# ide-8bit.net
KiCad netlist of a schematic drawn in EAGLE
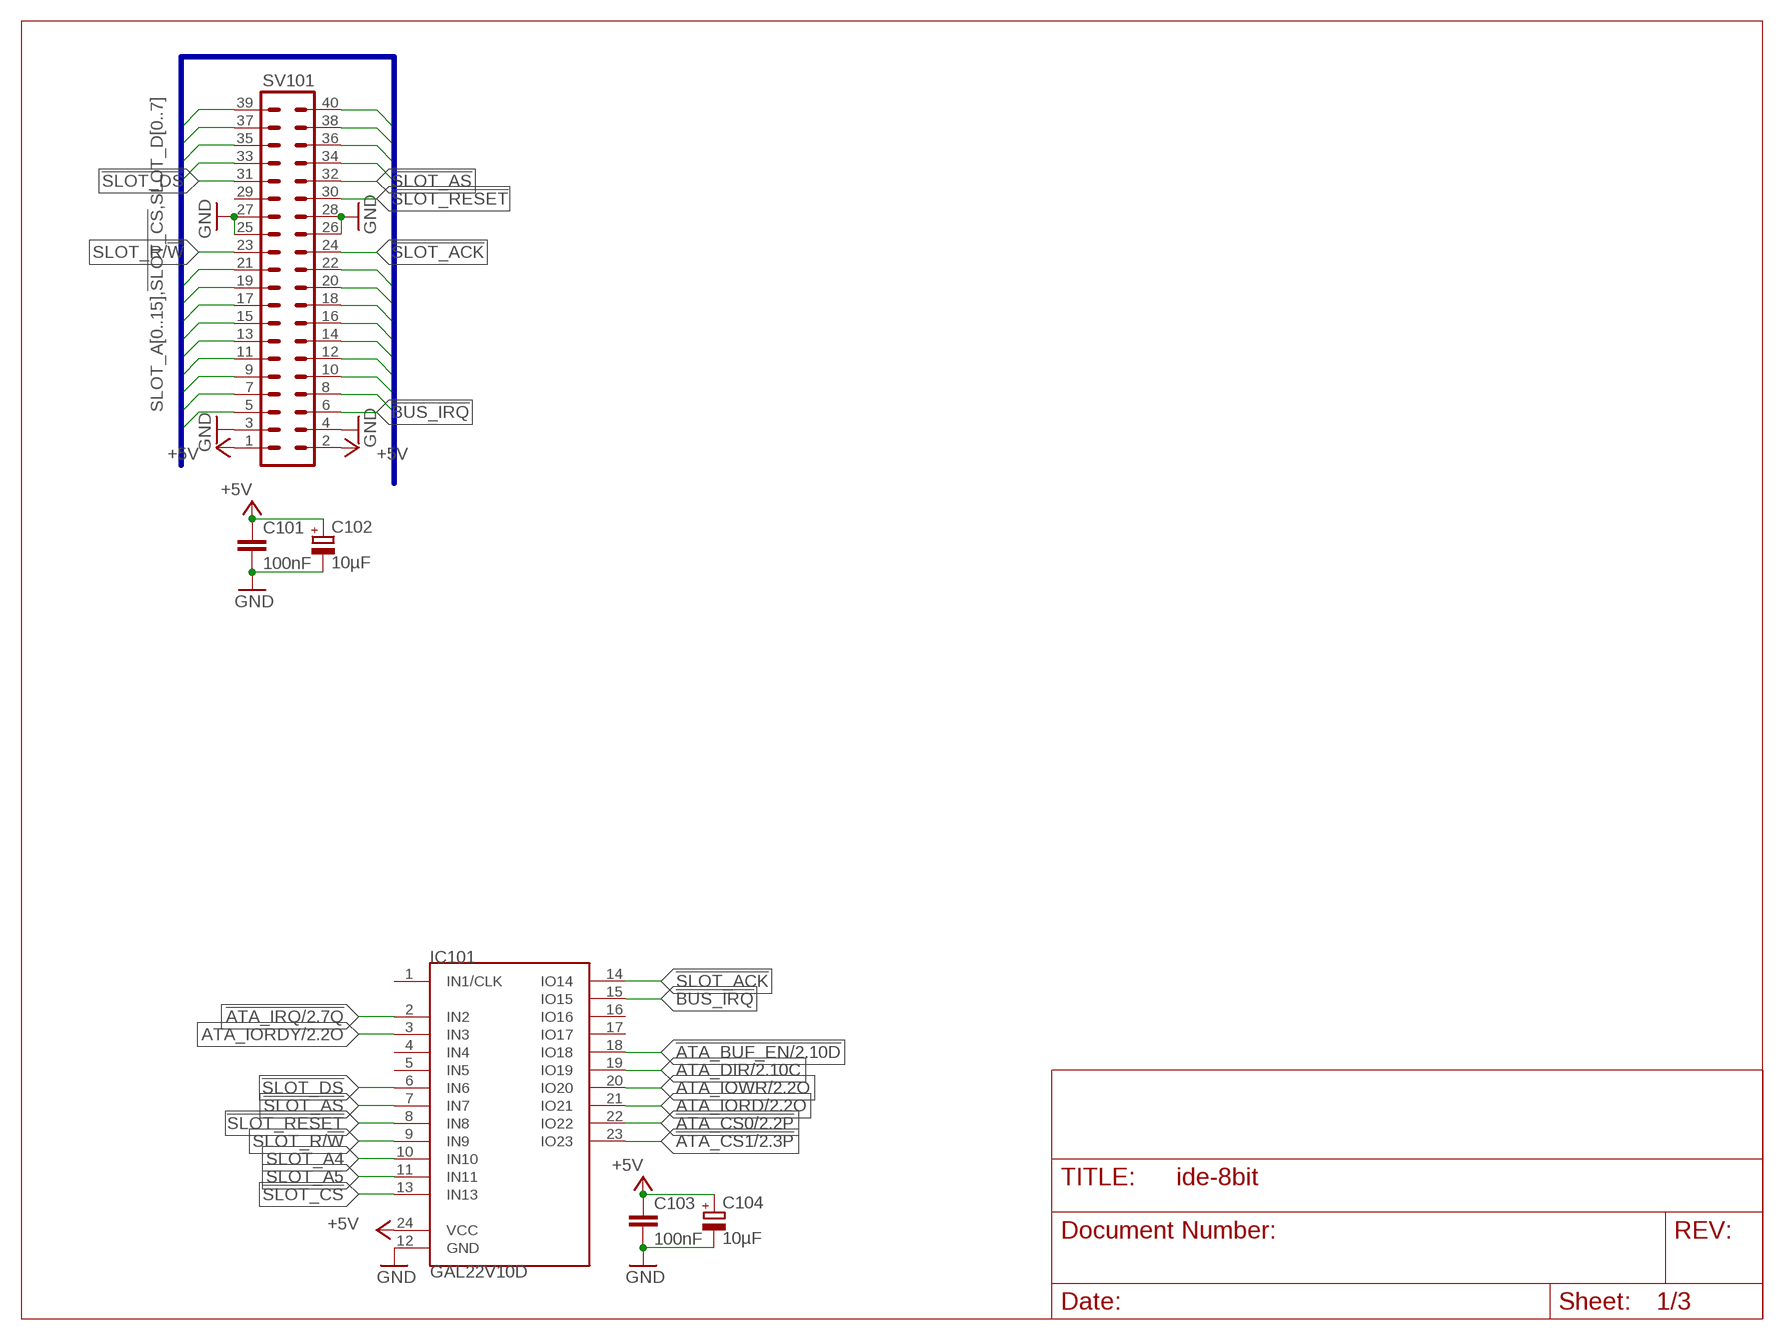
[diagram p0: schematic, sheet 1]
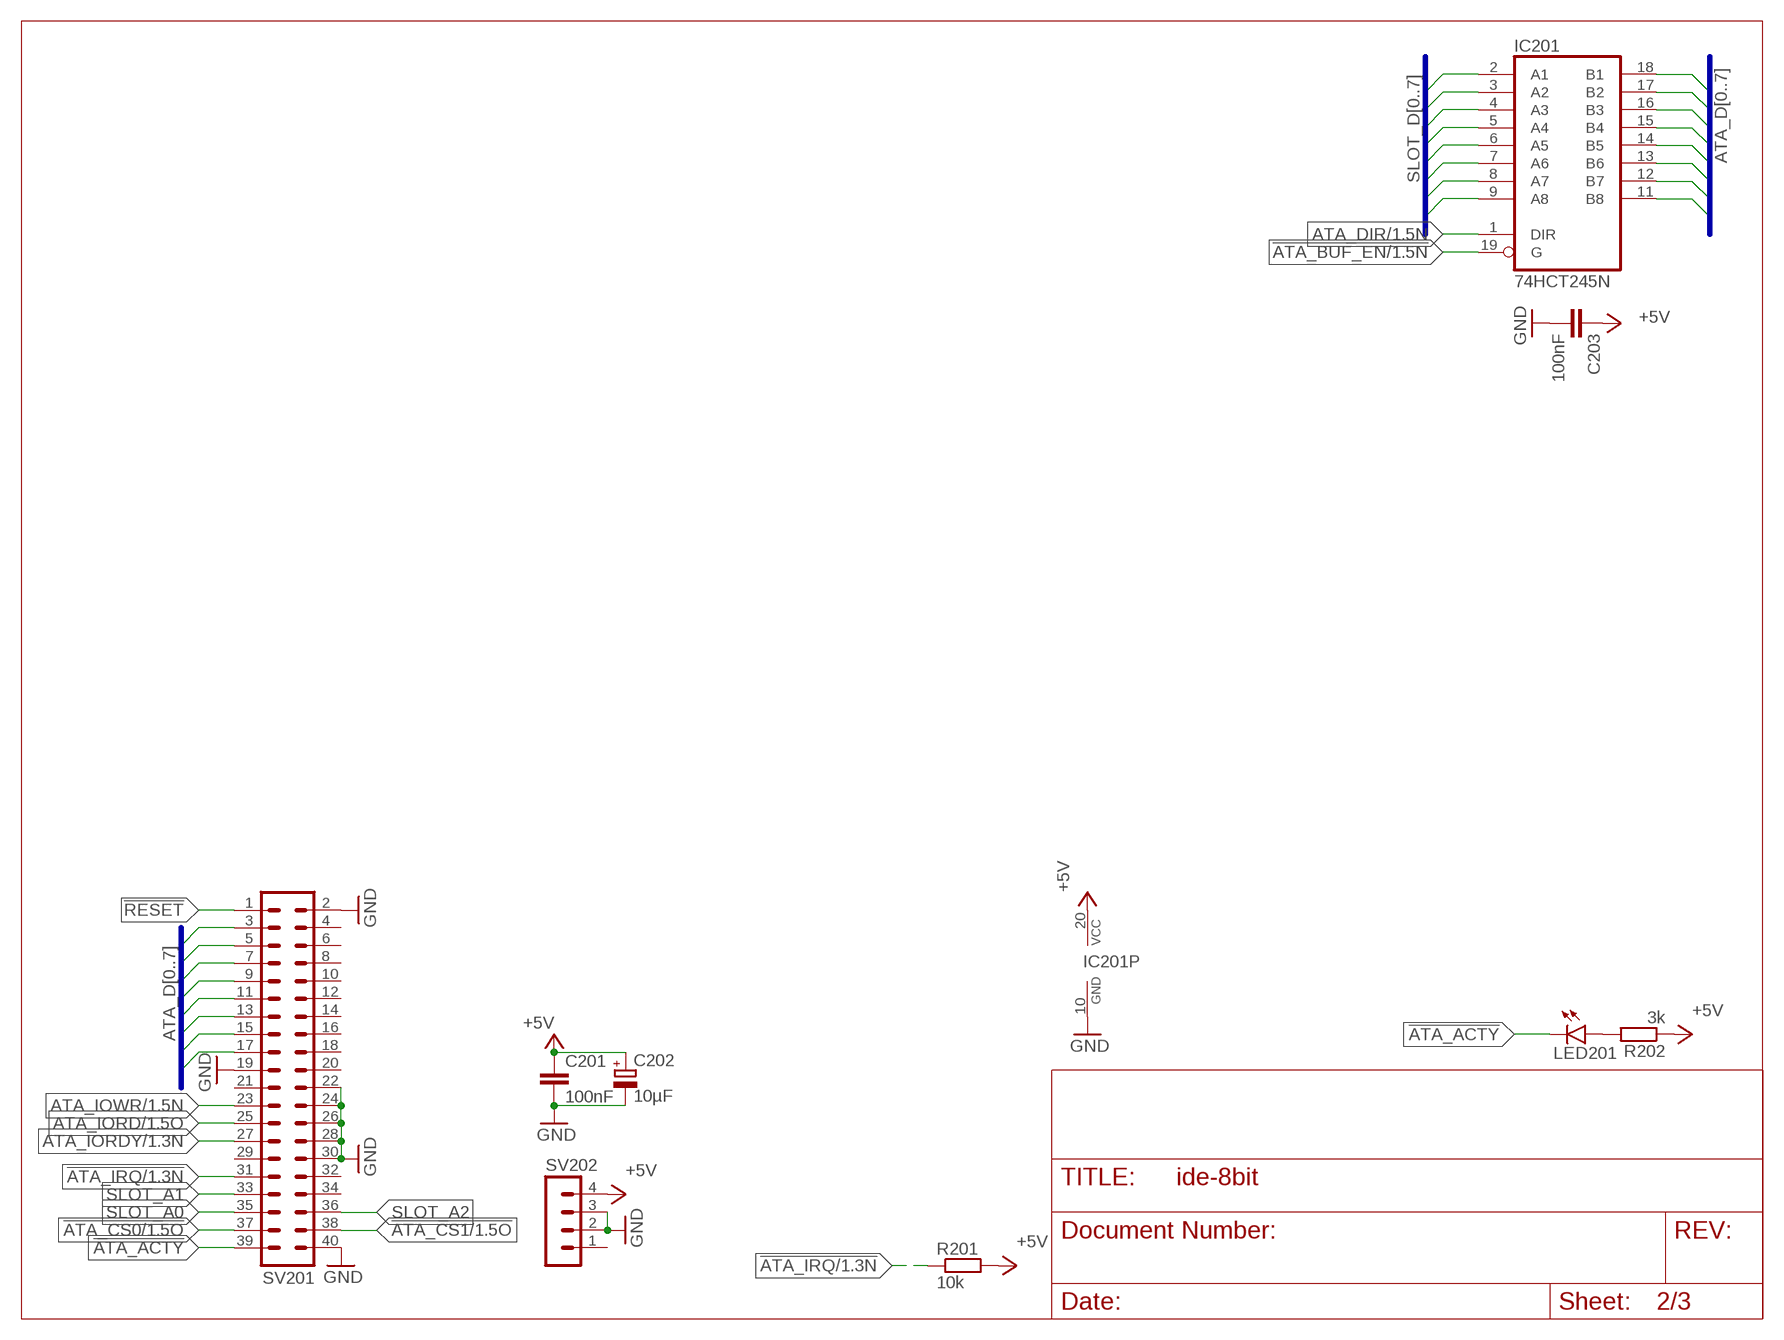
[diagram p1: schematic, sheet 2]
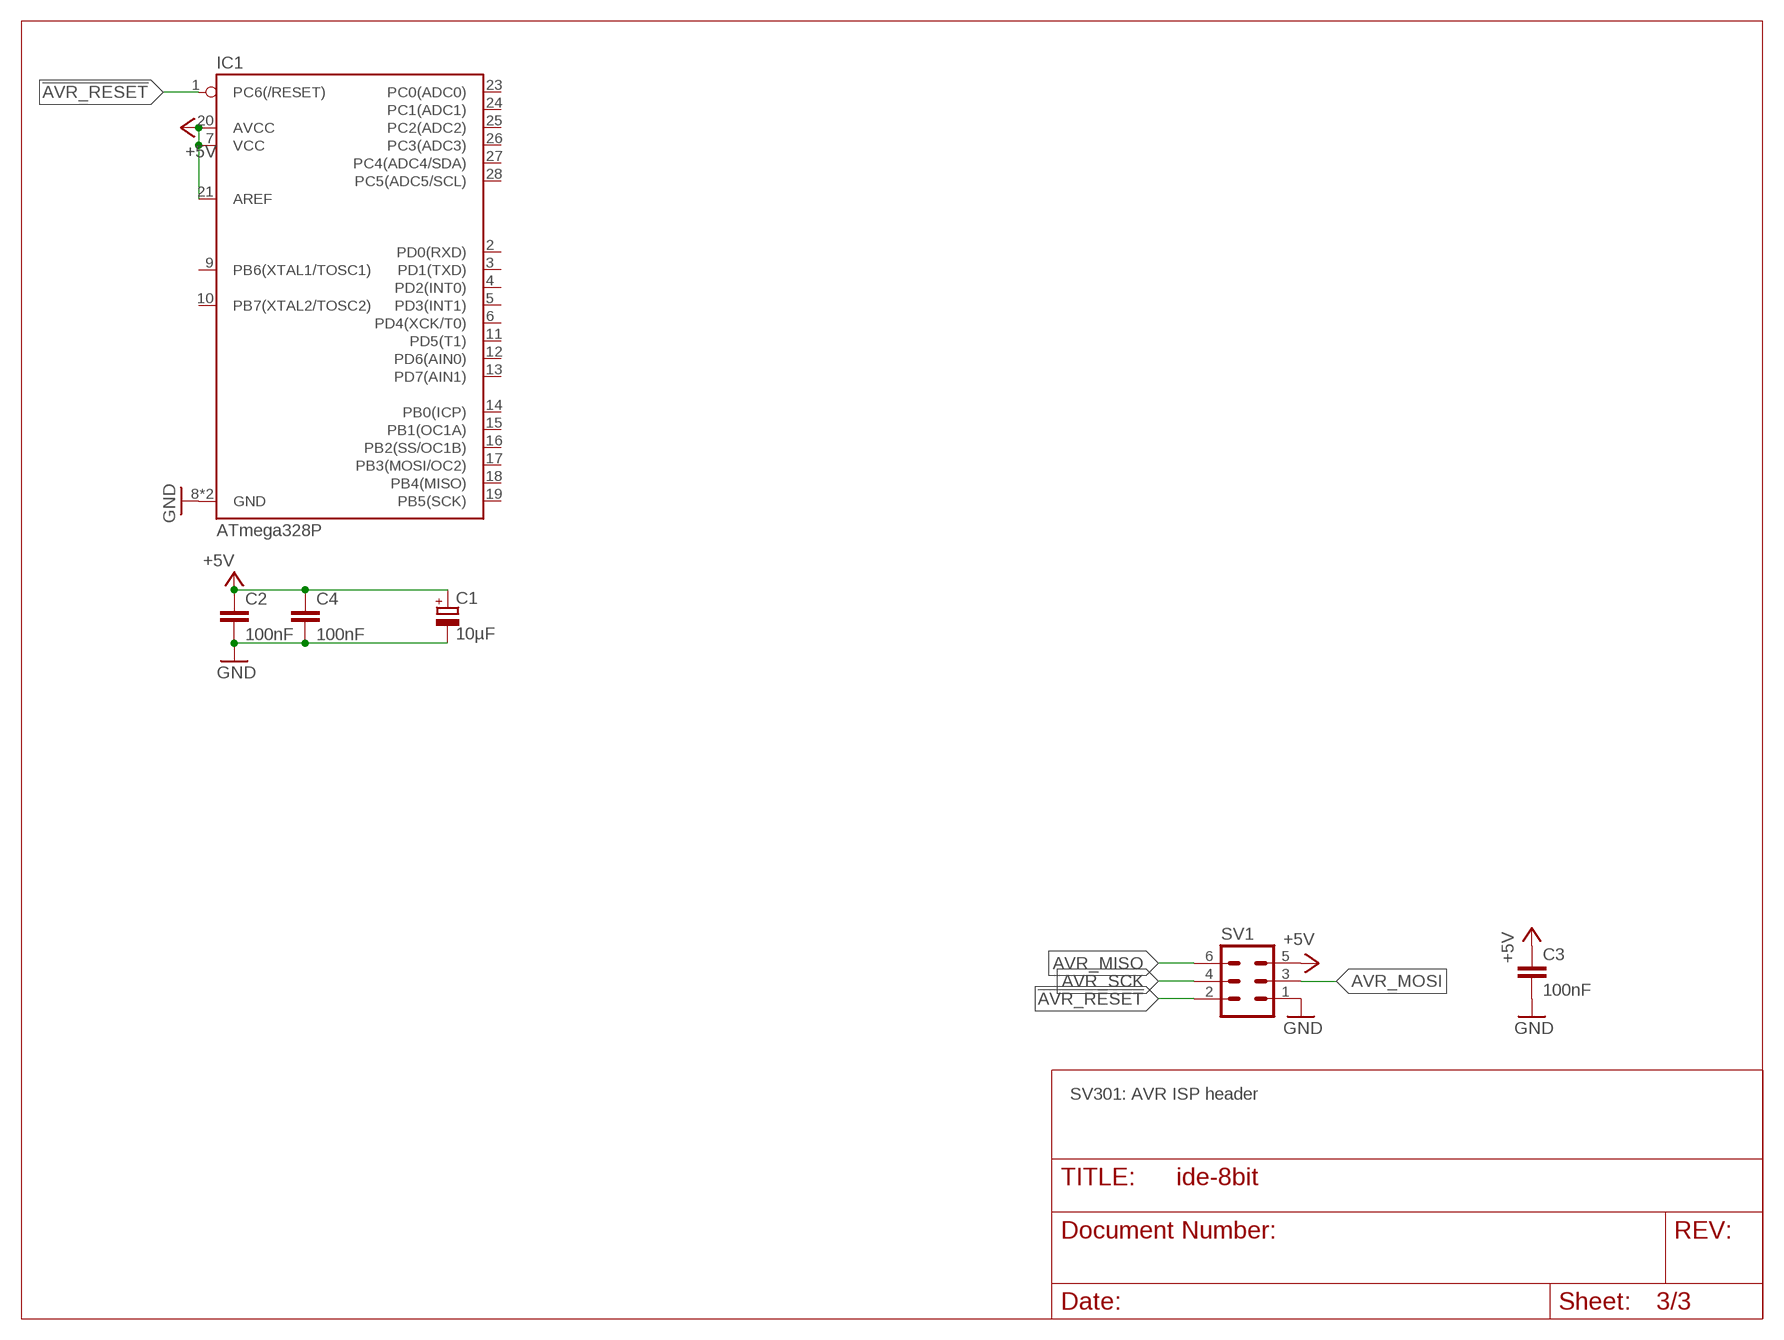
[diagram p2: schematic, sheet 3]

(export (version "E")
  (design (tool "Eeschema 10.0.6"))
  (components
    (comp (ref "C1")
      (value "10µF")
      (footprint "eagle-import:SMC_B")
      (libsource (lib "eagle-import") (part "CPOL-EUSMCB"))
    )
    (comp (ref "C2")
      (value "100nF")
      (footprint "eagle-import:C0805")
      (libsource (lib "eagle-import") (part "C-EUC0805"))
    )
    (comp (ref "C3")
      (value "100nF")
      (footprint "eagle-import:C0805")
      (libsource (lib "eagle-import") (part "C-EUC0805"))
    )
    (comp (ref "C4")
      (value "100nF")
      (footprint "eagle-import:C0805")
      (libsource (lib "eagle-import") (part "C-EUC0805"))
    )
    (comp (ref "IC1")
      (value "ATmega328P")
      (footprint "eagle-import:DIP28")
      (libsource (lib "eagle-import") (part "ATMEGA328P_PDIP"))
    )
    (comp (ref "SV1")
      (value "ML6")
      (footprint "eagle-import:ML6")
      (libsource (lib "eagle-import") (part "ML6"))
    )
    (comp (ref "C101")
      (value "100nF")
      (footprint "eagle-import:C0805")
      (libsource (lib "eagle-import") (part "C-EUC0805"))
    )
    (comp (ref "C102")
      (value "10µF")
      (footprint "eagle-import:SMC_B")
      (libsource (lib "eagle-import") (part "CPOL-EUSMCB"))
    )
    (comp (ref "C103")
      (value "100nF")
      (footprint "eagle-import:C0805")
      (libsource (lib "eagle-import") (part "C-EUC0805"))
    )
    (comp (ref "C104")
      (value "10µF")
      (footprint "eagle-import:SMC_B")
      (libsource (lib "eagle-import") (part "CPOL-EUSMCB"))
    )
    (comp (ref "IC101")
      (value "GAL22V10D")
      (footprint "eagle-import:DIL24S")
      (libsource (lib "eagle-import") (part "GAL22V10DIP24"))
    )
    (comp (ref "SV101")
      (value "MA20-2W")
      (footprint "eagle-import:MA20-2W")
      (libsource (lib "eagle-import") (part "MA20-2W"))
    )
    (comp (ref "C201")
      (value "100nF")
      (footprint "eagle-import:C0805")
      (libsource (lib "eagle-import") (part "C-EUC0805"))
    )
    (comp (ref "C202")
      (value "10µF")
      (footprint "eagle-import:SMC_B")
      (libsource (lib "eagle-import") (part "CPOL-EUSMCB"))
    )
    (comp (ref "C203")
      (value "100nF")
      (footprint "eagle-import:C0805")
      (libsource (lib "eagle-import") (part "C-EUC0805"))
    )
    (comp (ref "IC201")
      (value "74HCT245N")
      (footprint "eagle-import:DIL20")
      (fields (field (name "MOUSER") "595-SN74HCT245N") (field (name "MOUSER_SOCKET") "575-1104732041001000"))
      (libsource (lib "eagle-import") (part "74245NHCT"))
    )
    (comp (ref "LED201")
      (value "LEDCHIPLED_1206")
      (footprint "eagle-import:CHIPLED_1206")
      (libsource (lib "eagle-import") (part "LEDCHIPLED_1206"))
    )
    (comp (ref "R201")
      (value "10k")
      (footprint "eagle-import:R2012")
      (libsource (lib "eagle-import") (part "R-EU_R2012"))
    )
    (comp (ref "R202")
      (value "3k")
      (footprint "eagle-import:R2012")
      (libsource (lib "eagle-import") (part "R-EU_R2012"))
    )
    (comp (ref "SV201")
      (value "ML40L")
      (footprint "eagle-import:ML40L")
      (libsource (lib "eagle-import") (part "ML40L"))
    )
    (comp (ref "SV202")
      (value "MA04-1")
      (footprint "eagle-import:MA04-1")
      (libsource (lib "eagle-import") (part "MA04-1"))
    )
  )
  (nets
    (net (code "1") (name "+5V") (class "Default")
      (node (ref "C1") (pin "+") (pinfunction "+_+") (pintype "passive"))
      (node (ref "C101") (pin "1") (pinfunction "1_1") (pintype "passive"))
      (node (ref "C102") (pin "+") (pinfunction "+_+") (pintype "passive"))
      (node (ref "C103") (pin "1") (pinfunction "1_1") (pintype "passive"))
      (node (ref "C104") (pin "+") (pinfunction "+_+") (pintype "passive"))
      (node (ref "C2") (pin "1") (pinfunction "1_1") (pintype "passive"))
      (node (ref "C201") (pin "1") (pinfunction "1_1") (pintype "passive"))
      (node (ref "C202") (pin "+") (pinfunction "+_+") (pintype "passive"))
      (node (ref "C203") (pin "1") (pinfunction "1_1") (pintype "passive"))
      (node (ref "C3") (pin "1") (pinfunction "1_1") (pintype "passive"))
      (node (ref "C4") (pin "1") (pinfunction "1_1") (pintype "passive"))
      (node (ref "IC1") (pin "20") (pinfunction "AVCC_20") (pintype "bidirectional"))
      (node (ref "IC1") (pin "21") (pinfunction "AREF_21") (pintype "bidirectional"))
      (node (ref "IC1") (pin "7") (pinfunction "VCC_7") (pintype "bidirectional"))
      (node (ref "IC101") (pin "24") (pinfunction "VCC_24") (pintype "power_in"))
      (node (ref "IC201") (pin "20") (pinfunction "VCC_20") (pintype "power_in"))
      (node (ref "R201") (pin "2") (pinfunction "2_2") (pintype "passive"))
      (node (ref "R202") (pin "1") (pinfunction "1_1") (pintype "passive"))
      (node (ref "SV1") (pin "5") (pinfunction "5_5") (pintype "passive"))
      (node (ref "SV101") (pin "1") (pinfunction "1_1") (pintype "passive"))
      (node (ref "SV101") (pin "2") (pinfunction "2_2") (pintype "passive"))
      (node (ref "SV202") (pin "4") (pinfunction "4_4") (pintype "passive"))
    )
    (net (code "5") (name "ATA_D0") (class "Default")
      (node (ref "IC201") (pin "18") (pinfunction "B1_18") (pintype "bidirectional"))
      (node (ref "SV201") (pin "17") (pinfunction "17_17") (pintype "passive"))
    )
    (net (code "6") (name "ATA_D1") (class "Default")
      (node (ref "IC201") (pin "17") (pinfunction "B2_17") (pintype "bidirectional"))
      (node (ref "SV201") (pin "15") (pinfunction "15_15") (pintype "passive"))
    )
    (net (code "7") (name "ATA_D2") (class "Default")
      (node (ref "IC201") (pin "16") (pinfunction "B3_16") (pintype "bidirectional"))
      (node (ref "SV201") (pin "13") (pinfunction "13_13") (pintype "passive"))
    )
    (net (code "8") (name "ATA_D3") (class "Default")
      (node (ref "IC201") (pin "15") (pinfunction "B4_15") (pintype "bidirectional"))
      (node (ref "SV201") (pin "11") (pinfunction "11_11") (pintype "passive"))
    )
    (net (code "9") (name "ATA_D4") (class "Default")
      (node (ref "IC201") (pin "14") (pinfunction "B5_14") (pintype "bidirectional"))
      (node (ref "SV201") (pin "9") (pinfunction "9_9") (pintype "passive"))
    )
    (net (code "10") (name "ATA_D5") (class "Default")
      (node (ref "IC201") (pin "13") (pinfunction "B6_13") (pintype "bidirectional"))
      (node (ref "SV201") (pin "7") (pinfunction "7_7") (pintype "passive"))
    )
    (net (code "11") (name "ATA_D6") (class "Default")
      (node (ref "IC201") (pin "12") (pinfunction "B7_12") (pintype "bidirectional"))
      (node (ref "SV201") (pin "5") (pinfunction "5_5") (pintype "passive"))
    )
    (net (code "12") (name "ATA_D7") (class "Default")
      (node (ref "IC201") (pin "11") (pinfunction "B8_11") (pintype "bidirectional"))
      (node (ref "SV201") (pin "3") (pinfunction "3_3") (pintype "passive"))
    )
    (net (code "13") (name "ATA_DIR") (class "Default")
      (node (ref "IC101") (pin "19") (pinfunction "IO19_19") (pintype "bidirectional"))
      (node (ref "IC201") (pin "1") (pinfunction "DIR_1") (pintype "input"))
    )
    (net (code "14") (name "ATA_IORD") (class "Default")
      (node (ref "IC101") (pin "21") (pinfunction "IO21_21") (pintype "bidirectional"))
      (node (ref "SV201") (pin "25") (pinfunction "25_25") (pintype "passive"))
    )
    (net (code "15") (name "ATA_IORDY") (class "Default")
      (node (ref "IC101") (pin "3") (pinfunction "IN3_3") (pintype "input"))
      (node (ref "SV201") (pin "27") (pinfunction "27_27") (pintype "passive"))
    )
    (net (code "16") (name "ATA_IOWR") (class "Default")
      (node (ref "IC101") (pin "20") (pinfunction "IO20_20") (pintype "bidirectional"))
      (node (ref "SV201") (pin "23") (pinfunction "23_23") (pintype "passive"))
    )
    (net (code "17") (name "AVR_MISO") (class "Default")
      (node (ref "SV1") (pin "6") (pinfunction "6_6") (pintype "passive"))
    )
    (net (code "18") (name "AVR_MOSI") (class "Default")
      (node (ref "SV1") (pin "3") (pinfunction "3_3") (pintype "passive"))
    )
    (net (code "19") (name "AVR_SCK") (class "Default")
      (node (ref "SV1") (pin "4") (pinfunction "4_4") (pintype "passive"))
    )
    (net (code "20") (name "GND") (class "Default")
      (node (ref "C1") (pin "-") (pinfunction "-_-") (pintype "passive"))
      (node (ref "C101") (pin "2") (pinfunction "2_2") (pintype "passive"))
      (node (ref "C102") (pin "-") (pinfunction "-_-") (pintype "passive"))
      (node (ref "C103") (pin "2") (pinfunction "2_2") (pintype "passive"))
      (node (ref "C104") (pin "-") (pinfunction "-_-") (pintype "passive"))
      (node (ref "C2") (pin "2") (pinfunction "2_2") (pintype "passive"))
      (node (ref "C201") (pin "2") (pinfunction "2_2") (pintype "passive"))
      (node (ref "C202") (pin "-") (pinfunction "-_-") (pintype "passive"))
      (node (ref "C203") (pin "2") (pinfunction "2_2") (pintype "passive"))
      (node (ref "C3") (pin "2") (pinfunction "2_2") (pintype "passive"))
      (node (ref "C4") (pin "2") (pinfunction "2_2") (pintype "passive"))
      (node (ref "IC1") (pin "22") (pinfunction "GND_22") (pintype "bidirectional"))
      (node (ref "IC1") (pin "8") (pinfunction "GND_8") (pintype "bidirectional"))
      (node (ref "IC101") (pin "12") (pinfunction "GND_12") (pintype "power_in"))
      (node (ref "IC201") (pin "10") (pinfunction "GND_10") (pintype "power_in"))
      (node (ref "SV1") (pin "1") (pinfunction "1_1") (pintype "passive"))
      (node (ref "SV101") (pin "25") (pinfunction "25_25") (pintype "passive"))
      (node (ref "SV101") (pin "26") (pinfunction "26_26") (pintype "passive"))
      (node (ref "SV101") (pin "27") (pinfunction "27_27") (pintype "passive"))
      (node (ref "SV101") (pin "28") (pinfunction "28_28") (pintype "passive"))
      (node (ref "SV101") (pin "3") (pinfunction "3_3") (pintype "passive"))
      (node (ref "SV101") (pin "4") (pinfunction "4_4") (pintype "passive"))
      (node (ref "SV201") (pin "19") (pinfunction "19_19") (pintype "passive"))
      (node (ref "SV201") (pin "2") (pinfunction "2_2") (pintype "passive"))
      (node (ref "SV201") (pin "22") (pinfunction "22_22") (pintype "passive"))
      (node (ref "SV201") (pin "24") (pinfunction "24_24") (pintype "passive"))
      (node (ref "SV201") (pin "26") (pinfunction "26_26") (pintype "passive"))
      (node (ref "SV201") (pin "28") (pinfunction "28_28") (pintype "passive"))
      (node (ref "SV201") (pin "30") (pinfunction "30_30") (pintype "passive"))
      (node (ref "SV201") (pin "40") (pinfunction "40_40") (pintype "passive"))
      (node (ref "SV202") (pin "2") (pinfunction "2_2") (pintype "passive"))
      (node (ref "SV202") (pin "3") (pinfunction "3_3") (pintype "passive"))
    )
    (net (code "21") (name "Net-(LED201-PadA)") (class "Default")
      (node (ref "LED201") (pin "A") (pinfunction "A_A") (pintype "passive"))
      (node (ref "R202") (pin "2") (pinfunction "2_2") (pintype "passive"))
    )
    (net (code "22") (name "SLOT_A0") (class "Default")
      (node (ref "SV101") (pin "12") (pinfunction "12_12") (pintype "passive"))
      (node (ref "SV201") (pin "35") (pinfunction "35_35") (pintype "passive"))
    )
    (net (code "23") (name "SLOT_A1") (class "Default")
      (node (ref "SV101") (pin "10") (pinfunction "10_10") (pintype "passive"))
      (node (ref "SV201") (pin "33") (pinfunction "33_33") (pintype "passive"))
    )
    (net (code "24") (name "SLOT_A2") (class "Default")
      (node (ref "SV101") (pin "8") (pinfunction "8_8") (pintype "passive"))
      (node (ref "SV201") (pin "36") (pinfunction "36_36") (pintype "passive"))
    )
    (net (code "25") (name "SLOT_A4") (class "Default")
      (node (ref "IC101") (pin "10") (pinfunction "IN10_10") (pintype "input"))
      (node (ref "SV101") (pin "9") (pinfunction "9_9") (pintype "passive"))
    )
    (net (code "26") (name "SLOT_A5") (class "Default")
      (node (ref "IC101") (pin "11") (pinfunction "IN11_11") (pintype "input"))
      (node (ref "SV101") (pin "11") (pinfunction "11_11") (pintype "passive"))
    )
    (net (code "27") (name "SLOT_D0") (class "Default")
      (node (ref "IC201") (pin "2") (pinfunction "A1_2") (pintype "bidirectional"))
      (node (ref "SV101") (pin "35") (pinfunction "35_35") (pintype "passive"))
    )
    (net (code "28") (name "SLOT_D1") (class "Default")
      (node (ref "IC201") (pin "3") (pinfunction "A2_3") (pintype "bidirectional"))
      (node (ref "SV101") (pin "37") (pinfunction "37_37") (pintype "passive"))
    )
    (net (code "29") (name "SLOT_D2") (class "Default")
      (node (ref "IC201") (pin "4") (pinfunction "A3_4") (pintype "bidirectional"))
      (node (ref "SV101") (pin "39") (pinfunction "39_39") (pintype "passive"))
    )
    (net (code "30") (name "SLOT_D3") (class "Default")
      (node (ref "IC201") (pin "5") (pinfunction "A4_5") (pintype "bidirectional"))
      (node (ref "SV101") (pin "40") (pinfunction "40_40") (pintype "passive"))
    )
    (net (code "31") (name "SLOT_D4") (class "Default")
      (node (ref "IC201") (pin "6") (pinfunction "A5_6") (pintype "bidirectional"))
      (node (ref "SV101") (pin "38") (pinfunction "38_38") (pintype "passive"))
    )
    (net (code "32") (name "SLOT_D5") (class "Default")
      (node (ref "IC201") (pin "7") (pinfunction "A6_7") (pintype "bidirectional"))
      (node (ref "SV101") (pin "36") (pinfunction "36_36") (pintype "passive"))
    )
    (net (code "33") (name "SLOT_D6") (class "Default")
      (node (ref "IC201") (pin "8") (pinfunction "A7_8") (pintype "bidirectional"))
      (node (ref "SV101") (pin "34") (pinfunction "34_34") (pintype "passive"))
    )
    (net (code "34") (name "SLOT_D7") (class "Default")
      (node (ref "IC201") (pin "9") (pinfunction "A8_9") (pintype "bidirectional"))
      (node (ref "SV101") (pin "33") (pinfunction "33_33") (pintype "passive"))
    )
    (net (code "35") (name "SLOT_R{slash}~{W}") (class "Default")
      (node (ref "IC101") (pin "9") (pinfunction "IN9_9") (pintype "input"))
      (node (ref "SV101") (pin "23") (pinfunction "23_23") (pintype "passive"))
    )
    (net (code "36") (name "unconnected-(IC1-PB0(ICP)-Pad14)") (class "Default")
      (node (ref "IC1") (pin "14") (pinfunction "PB0(ICP)_14") (pintype "bidirectional"))
    )
    (net (code "37") (name "unconnected-(IC1-PB1(OC1A)-Pad15)") (class "Default")
      (node (ref "IC1") (pin "15") (pinfunction "PB1(OC1A)_15") (pintype "bidirectional"))
    )
    (net (code "38") (name "unconnected-(IC1-PB2(SS{slash}OC1B)-Pad16)") (class "Default")
      (node (ref "IC1") (pin "16") (pinfunction "PB2(SS/OC1B)_16") (pintype "bidirectional"))
    )
    (net (code "39") (name "unconnected-(IC1-PB3(MOSI{slash}OC2)-Pad17)") (class "Default")
      (node (ref "IC1") (pin "17") (pinfunction "PB3(MOSI/OC2)_17") (pintype "bidirectional"))
    )
    (net (code "40") (name "unconnected-(IC1-PB4(MISO)-Pad18)") (class "Default")
      (node (ref "IC1") (pin "18") (pinfunction "PB4(MISO)_18") (pintype "bidirectional"))
    )
    (net (code "41") (name "unconnected-(IC1-PB5(SCK)-Pad19)") (class "Default")
      (node (ref "IC1") (pin "19") (pinfunction "PB5(SCK)_19") (pintype "bidirectional"))
    )
    (net (code "42") (name "unconnected-(IC1-PB6(XTAL1{slash}TOSC1)-Pad9)") (class "Default")
      (node (ref "IC1") (pin "9") (pinfunction "PB6(XTAL1/TOSC1)_9") (pintype "bidirectional"))
    )
    (net (code "43") (name "unconnected-(IC1-PB7(XTAL2{slash}TOSC2)-Pad10)") (class "Default")
      (node (ref "IC1") (pin "10") (pinfunction "PB7(XTAL2/TOSC2)_10") (pintype "bidirectional"))
    )
    (net (code "44") (name "unconnected-(IC1-PC0(ADC0)-Pad23)") (class "Default")
      (node (ref "IC1") (pin "23") (pinfunction "PC0(ADC0)_23") (pintype "bidirectional"))
    )
    (net (code "45") (name "unconnected-(IC1-PC1(ADC1)-Pad24)") (class "Default")
      (node (ref "IC1") (pin "24") (pinfunction "PC1(ADC1)_24") (pintype "bidirectional"))
    )
    (net (code "46") (name "unconnected-(IC1-PC2(ADC2)-Pad25)") (class "Default")
      (node (ref "IC1") (pin "25") (pinfunction "PC2(ADC2)_25") (pintype "bidirectional"))
    )
    (net (code "47") (name "unconnected-(IC1-PC3(ADC3)-Pad26)") (class "Default")
      (node (ref "IC1") (pin "26") (pinfunction "PC3(ADC3)_26") (pintype "bidirectional"))
    )
    (net (code "48") (name "unconnected-(IC1-PC4(ADC4{slash}SDA)-Pad27)") (class "Default")
      (node (ref "IC1") (pin "27") (pinfunction "PC4(ADC4/SDA)_27") (pintype "bidirectional"))
    )
    (net (code "49") (name "unconnected-(IC1-PC5(ADC5{slash}SCL)-Pad28)") (class "Default")
      (node (ref "IC1") (pin "28") (pinfunction "PC5(ADC5/SCL)_28") (pintype "bidirectional"))
    )
    (net (code "50") (name "unconnected-(IC1-PD0(RXD)-Pad2)") (class "Default")
      (node (ref "IC1") (pin "2") (pinfunction "PD0(RXD)_2") (pintype "bidirectional"))
    )
    (net (code "51") (name "unconnected-(IC1-PD1(TXD)-Pad3)") (class "Default")
      (node (ref "IC1") (pin "3") (pinfunction "PD1(TXD)_3") (pintype "bidirectional"))
    )
    (net (code "52") (name "unconnected-(IC1-PD2(INT0)-Pad4)") (class "Default")
      (node (ref "IC1") (pin "4") (pinfunction "PD2(INT0)_4") (pintype "bidirectional"))
    )
    (net (code "53") (name "unconnected-(IC1-PD3(INT1)-Pad5)") (class "Default")
      (node (ref "IC1") (pin "5") (pinfunction "PD3(INT1)_5") (pintype "bidirectional"))
    )
    (net (code "54") (name "unconnected-(IC1-PD4(XCK{slash}T0)-Pad6)") (class "Default")
      (node (ref "IC1") (pin "6") (pinfunction "PD4(XCK/T0)_6") (pintype "bidirectional"))
    )
    (net (code "55") (name "unconnected-(IC1-PD5(T1)-Pad11)") (class "Default")
      (node (ref "IC1") (pin "11") (pinfunction "PD5(T1)_11") (pintype "bidirectional"))
    )
    (net (code "56") (name "unconnected-(IC1-PD6(AIN0)-Pad12)") (class "Default")
      (node (ref "IC1") (pin "12") (pinfunction "PD6(AIN0)_12") (pintype "bidirectional"))
    )
    (net (code "57") (name "unconnected-(IC1-PD7(AIN1)-Pad13)") (class "Default")
      (node (ref "IC1") (pin "13") (pinfunction "PD7(AIN1)_13") (pintype "bidirectional"))
    )
    (net (code "58") (name "unconnected-(IC101-IN1{slash}CLK-Pad1)") (class "Default")
      (node (ref "IC101") (pin "1") (pinfunction "IN1/CLK_1") (pintype "input"))
    )
    (net (code "59") (name "unconnected-(IC101-IN4-Pad4)") (class "Default")
      (node (ref "IC101") (pin "4") (pinfunction "IN4_4") (pintype "input"))
    )
    (net (code "60") (name "unconnected-(IC101-IN5-Pad5)") (class "Default")
      (node (ref "IC101") (pin "5") (pinfunction "IN5_5") (pintype "input"))
    )
    (net (code "61") (name "unconnected-(IC101-IO16-Pad16)") (class "Default")
      (node (ref "IC101") (pin "16") (pinfunction "IO16_16") (pintype "bidirectional"))
    )
    (net (code "62") (name "unconnected-(IC101-IO17-Pad17)") (class "Default")
      (node (ref "IC101") (pin "17") (pinfunction "IO17_17") (pintype "bidirectional"))
    )
    (net (code "63") (name "unconnected-(SV101-Pad7)") (class "Default")
      (node (ref "SV101") (pin "7") (pinfunction "7_7") (pintype "passive"))
    )
    (net (code "64") (name "unconnected-(SV101-Pad13)") (class "Default")
      (node (ref "SV101") (pin "13") (pinfunction "13_13") (pintype "passive"))
    )
    (net (code "65") (name "unconnected-(SV101-Pad14)") (class "Default")
      (node (ref "SV101") (pin "14") (pinfunction "14_14") (pintype "passive"))
    )
    (net (code "66") (name "unconnected-(SV101-Pad15)") (class "Default")
      (node (ref "SV101") (pin "15") (pinfunction "15_15") (pintype "passive"))
    )
    (net (code "67") (name "unconnected-(SV101-Pad16)") (class "Default")
      (node (ref "SV101") (pin "16") (pinfunction "16_16") (pintype "passive"))
    )
    (net (code "68") (name "unconnected-(SV101-Pad17)") (class "Default")
      (node (ref "SV101") (pin "17") (pinfunction "17_17") (pintype "passive"))
    )
    (net (code "69") (name "unconnected-(SV101-Pad18)") (class "Default")
      (node (ref "SV101") (pin "18") (pinfunction "18_18") (pintype "passive"))
    )
    (net (code "70") (name "unconnected-(SV101-Pad19)") (class "Default")
      (node (ref "SV101") (pin "19") (pinfunction "19_19") (pintype "passive"))
    )
    (net (code "71") (name "unconnected-(SV101-Pad20)") (class "Default")
      (node (ref "SV101") (pin "20") (pinfunction "20_20") (pintype "passive"))
    )
    (net (code "72") (name "unconnected-(SV101-Pad21)") (class "Default")
      (node (ref "SV101") (pin "21") (pinfunction "21_21") (pintype "passive"))
    )
    (net (code "73") (name "unconnected-(SV101-Pad22)") (class "Default")
      (node (ref "SV101") (pin "22") (pinfunction "22_22") (pintype "passive"))
    )
    (net (code "74") (name "unconnected-(SV101-Pad29)") (class "Default")
      (node (ref "SV101") (pin "29") (pinfunction "29_29") (pintype "passive"))
    )
    (net (code "75") (name "unconnected-(SV201-Pad4)") (class "Default")
      (node (ref "SV201") (pin "4") (pinfunction "4_4") (pintype "passive"))
    )
    (net (code "76") (name "unconnected-(SV201-Pad6)") (class "Default")
      (node (ref "SV201") (pin "6") (pinfunction "6_6") (pintype "passive"))
    )
    (net (code "77") (name "unconnected-(SV201-Pad8)") (class "Default")
      (node (ref "SV201") (pin "8") (pinfunction "8_8") (pintype "passive"))
    )
    (net (code "78") (name "unconnected-(SV201-Pad10)") (class "Default")
      (node (ref "SV201") (pin "10") (pinfunction "10_10") (pintype "passive"))
    )
    (net (code "79") (name "unconnected-(SV201-Pad12)") (class "Default")
      (node (ref "SV201") (pin "12") (pinfunction "12_12") (pintype "passive"))
    )
    (net (code "80") (name "unconnected-(SV201-Pad14)") (class "Default")
      (node (ref "SV201") (pin "14") (pinfunction "14_14") (pintype "passive"))
    )
    (net (code "81") (name "unconnected-(SV201-Pad16)") (class "Default")
      (node (ref "SV201") (pin "16") (pinfunction "16_16") (pintype "passive"))
    )
    (net (code "82") (name "unconnected-(SV201-Pad18)") (class "Default")
      (node (ref "SV201") (pin "18") (pinfunction "18_18") (pintype "passive"))
    )
    (net (code "83") (name "unconnected-(SV201-Pad20)") (class "Default")
      (node (ref "SV201") (pin "20") (pinfunction "20_20") (pintype "passive"))
    )
    (net (code "84") (name "unconnected-(SV201-Pad21)") (class "Default")
      (node (ref "SV201") (pin "21") (pinfunction "21_21") (pintype "passive"))
    )
    (net (code "85") (name "unconnected-(SV201-Pad29)") (class "Default")
      (node (ref "SV201") (pin "29") (pinfunction "29_29") (pintype "passive"))
    )
    (net (code "86") (name "unconnected-(SV201-Pad32)") (class "Default")
      (node (ref "SV201") (pin "32") (pinfunction "32_32") (pintype "passive"))
    )
    (net (code "87") (name "unconnected-(SV201-Pad34)") (class "Default")
      (node (ref "SV201") (pin "34") (pinfunction "34_34") (pintype "passive"))
    )
    (net (code "88") (name "unconnected-(SV202-Pad1)") (class "Default")
      (node (ref "SV202") (pin "1") (pinfunction "1_1") (pintype "passive"))
    )
    (net (code "89") (name "~{ATA_ACTY}") (class "Default")
      (node (ref "LED201") (pin "C") (pinfunction "C_C") (pintype "passive"))
      (node (ref "SV201") (pin "39") (pinfunction "39_39") (pintype "passive"))
    )
    (net (code "90") (name "~{ATA_BUF_EN}") (class "Default")
      (node (ref "IC101") (pin "18") (pinfunction "IO18_18") (pintype "bidirectional"))
      (node (ref "IC201") (pin "19") (pinfunction "G_19") (pintype "input"))
    )
    (net (code "91") (name "~{ATA_CS0}") (class "Default")
      (node (ref "IC101") (pin "22") (pinfunction "IO22_22") (pintype "bidirectional"))
      (node (ref "SV201") (pin "37") (pinfunction "37_37") (pintype "passive"))
    )
    (net (code "92") (name "~{ATA_CS1}") (class "Default")
      (node (ref "IC101") (pin "23") (pinfunction "IO23_23") (pintype "bidirectional"))
      (node (ref "SV201") (pin "38") (pinfunction "38_38") (pintype "passive"))
    )
    (net (code "93") (name "~{ATA_IRQ}") (class "Default")
      (node (ref "IC101") (pin "2") (pinfunction "IN2_2") (pintype "input"))
      (node (ref "R201") (pin "1") (pinfunction "1_1") (pintype "passive"))
      (node (ref "SV201") (pin "31") (pinfunction "31_31") (pintype "passive"))
    )
    (net (code "94") (name "~{AVR_RESET}") (class "Default")
      (node (ref "IC1") (pin "1") (pinfunction "PC6(/RESET)_1") (pintype "bidirectional"))
      (node (ref "SV1") (pin "2") (pinfunction "2_2") (pintype "passive"))
    )
    (net (code "95") (name "~{BUS_IRQ}") (class "Default")
      (node (ref "IC101") (pin "15") (pinfunction "IO15_15") (pintype "bidirectional"))
      (node (ref "SV101") (pin "6") (pinfunction "6_6") (pintype "passive"))
    )
    (net (code "96") (name "~{RESET}") (class "Default")
      (node (ref "SV201") (pin "1") (pinfunction "1_1") (pintype "passive"))
    )
    (net (code "97") (name "~{SLOT_ACK}") (class "Default")
      (node (ref "IC101") (pin "14") (pinfunction "IO14_14") (pintype "bidirectional"))
      (node (ref "SV101") (pin "24") (pinfunction "24_24") (pintype "passive"))
    )
    (net (code "98") (name "~{SLOT_AS}") (class "Default")
      (node (ref "IC101") (pin "7") (pinfunction "IN7_7") (pintype "input"))
      (node (ref "SV101") (pin "32") (pinfunction "32_32") (pintype "passive"))
    )
    (net (code "99") (name "~{SLOT_CS}") (class "Default")
      (node (ref "IC101") (pin "13") (pinfunction "IN13_13") (pintype "input"))
      (node (ref "SV101") (pin "5") (pinfunction "5_5") (pintype "passive"))
    )
    (net (code "100") (name "~{SLOT_DS}") (class "Default")
      (node (ref "IC101") (pin "6") (pinfunction "IN6_6") (pintype "input"))
      (node (ref "SV101") (pin "31") (pinfunction "31_31") (pintype "passive"))
    )
    (net (code "101") (name "~{SLOT_RESET}") (class "Default")
      (node (ref "IC101") (pin "8") (pinfunction "IN8_8") (pintype "input"))
      (node (ref "SV101") (pin "30") (pinfunction "30_30") (pintype "passive"))
    )
  )
)
